# Camera_Schematics.net
KiCad netlist of a schematic drawn in Altium Designer
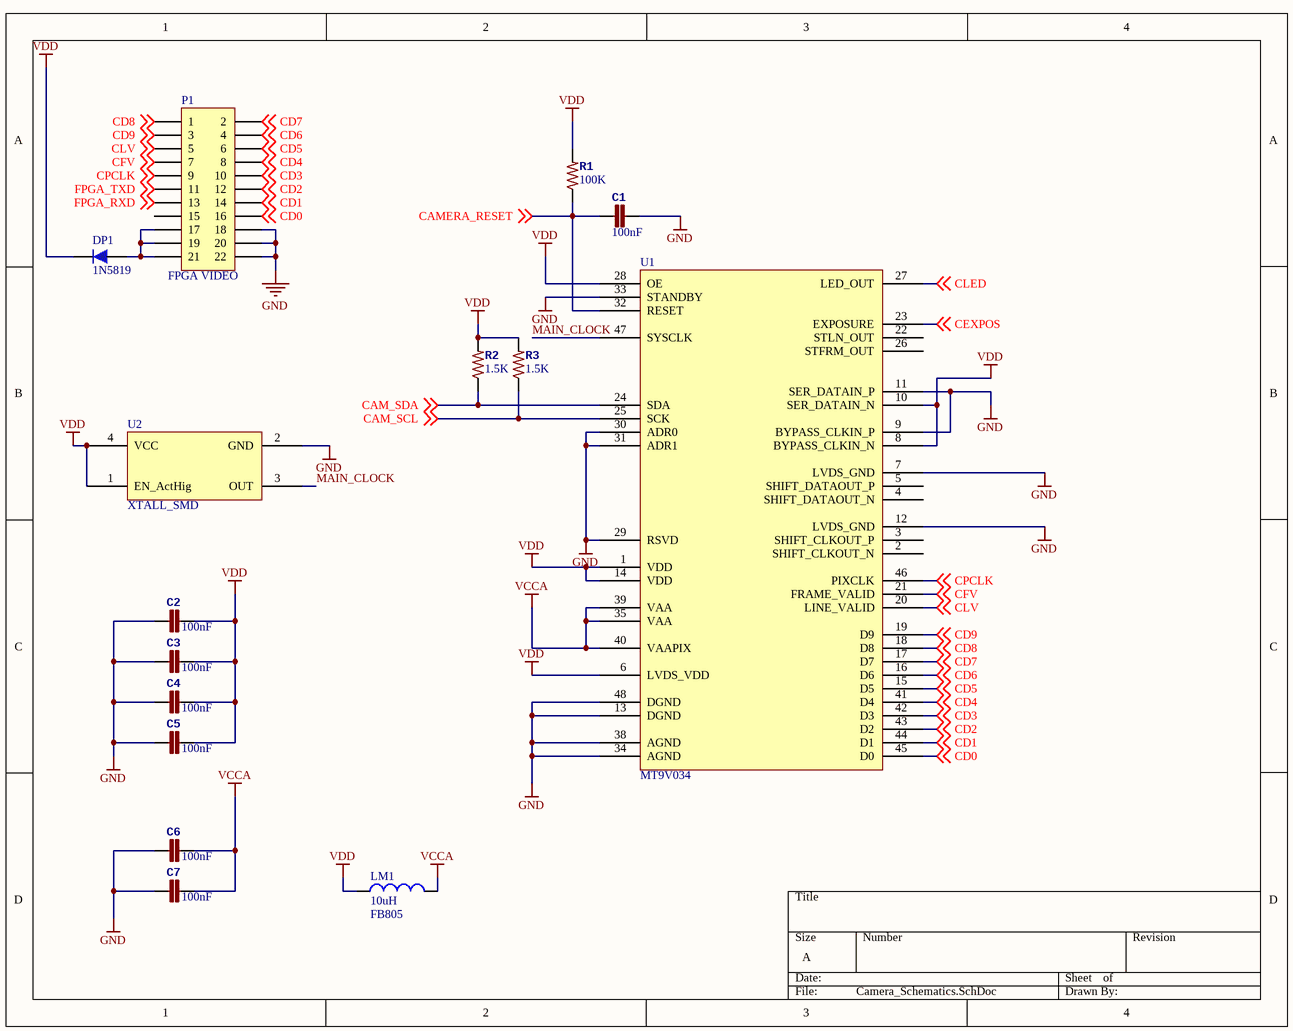
[diagram p0: Camera_Schematics.SchDoc]

(export (version "E")
  (design (tool "Eeschema 10.0.6"))
  (components
    (comp (ref "C1")
      (value "100nF")
      (footprint "_0805")
      (fields (field (name "Comment") "Cap"))
      (libsource (lib "Passives_Integrated_Library") (part "Cap_1"))
    )
    (comp (ref "C2")
      (value "100nF")
      (footprint "_0805")
      (fields (field (name "Comment") "Cap"))
      (libsource (lib "Passives_Integrated_Library") (part "Cap_1"))
    )
    (comp (ref "C3")
      (value "100nF")
      (footprint "_0805")
      (fields (field (name "Comment") "Cap"))
      (libsource (lib "Passives_Integrated_Library") (part "Cap_1"))
    )
    (comp (ref "C4")
      (value "100nF")
      (footprint "_0805")
      (fields (field (name "Comment") "Cap"))
      (libsource (lib "Passives_Integrated_Library") (part "Cap_1"))
    )
    (comp (ref "C5")
      (value "100nF")
      (footprint "_0805")
      (fields (field (name "Comment") "Cap"))
      (libsource (lib "Passives_Integrated_Library") (part "Cap_1"))
    )
    (comp (ref "C6")
      (value "100nF")
      (footprint "_0805")
      (fields (field (name "Comment") "Cap"))
      (libsource (lib "Passives_Integrated_Library") (part "Cap_1"))
    )
    (comp (ref "C7")
      (value "100nF")
      (footprint "_0805")
      (fields (field (name "Comment") "Cap"))
      (libsource (lib "Passives_Integrated_Library") (part "Cap_1"))
    )
    (comp (ref "DP1")
      (value "1N5819")
      (footprint "430X270D")
      (description "Schottkey Rectifiers")
      (fields (field (name "DESIGNER") "Abbas Basereh"))
      (libsource (lib "Diodes_Integrated_Library") (part "1N5819"))
    )
    (comp (ref "LM1")
      (value "10uH")
      (footprint "0805L")
      (description "Inductor")
      (fields (field (name "ALTIUM_VALUE") "FB805") (field (name "PUBLISHER") "Altium Limited"))
      (libsource (lib "Passives_Integrated_Library") (part "L SMA 0.25W"))
    )
    (comp (ref "P1")
      (value "FPGA VIDEO")
      (footprint "HDR2X11")
      (description "Header, 11-Pin, Dual row")
      (fields (field (name "PUBLISHER") "Altium Limited"))
      (libsource (lib "Miscellaneous Connectors") (part "Header 11X2"))
    )
    (comp (ref "R1")
      (value "100K")
      (footprint "_0603")
      (fields (field (name "Comment") "Resistor"))
      (libsource (lib "Passives_Integrated_Library") (part "Resistor"))
    )
    (comp (ref "R2")
      (value "1.5K")
      (footprint "_0603")
      (fields (field (name "Comment") "Resistor"))
      (libsource (lib "Passives_Integrated_Library") (part "Resistor"))
    )
    (comp (ref "R3")
      (value "1.5K")
      (footprint "_0603")
      (fields (field (name "Comment") "Resistor"))
      (libsource (lib "Passives_Integrated_Library") (part "Resistor"))
    )
    (comp (ref "U1")
      (value "MT9V034")
      (footprint "MT9V034")
      (libsource (lib "Sensors_Integrated_Library") (part "MT9V034"))
    )
    (comp (ref "U2")
      (value "XTALL_SMD")
      (footprint "XTAL_SMD")
      (libsource (lib "Passives_Integrated_Library") (part "XTAL_SMD"))
    )
  )
  (nets
    (net (code "1") (name "/MAIN_CLOCK") (class "Default")
      (node (ref "U1") (pin "47") (pinfunction "SYSCLK_47") (pintype "passive"))
      (node (ref "U2") (pin "3") (pinfunction "OUT_3") (pintype "passive"))
    )
    (net (code "2") (name "CAMERA_RESET") (class "Default")
      (node (ref "C1") (pin "1") (pinfunction "1_1") (pintype "passive"))
      (node (ref "R1") (pin "1") (pinfunction "1_1") (pintype "passive"))
      (node (ref "U1") (pin "32") (pinfunction "RESET_32") (pintype "passive"))
    )
    (net (code "3") (name "CAM_SCL") (class "Default")
      (node (ref "R3") (pin "1") (pinfunction "1_1") (pintype "passive"))
      (node (ref "U1") (pin "25") (pinfunction "SCK_25") (pintype "passive"))
    )
    (net (code "4") (name "CAM_SDA") (class "Default")
      (node (ref "R2") (pin "1") (pinfunction "1_1") (pintype "passive"))
      (node (ref "U1") (pin "24") (pinfunction "SDA_24") (pintype "passive"))
    )
    (net (code "5") (name "CD0") (class "Default")
      (node (ref "P1") (pin "16") (pinfunction "16_16") (pintype "passive"))
      (node (ref "U1") (pin "45") (pinfunction "D0_45") (pintype "passive"))
    )
    (net (code "6") (name "CD1") (class "Default")
      (node (ref "P1") (pin "14") (pinfunction "14_14") (pintype "passive"))
      (node (ref "U1") (pin "44") (pinfunction "D1_44") (pintype "passive"))
    )
    (net (code "7") (name "CD2") (class "Default")
      (node (ref "P1") (pin "12") (pinfunction "12_12") (pintype "passive"))
      (node (ref "U1") (pin "43") (pinfunction "D2_43") (pintype "passive"))
    )
    (net (code "8") (name "CD3") (class "Default")
      (node (ref "P1") (pin "10") (pinfunction "10_10") (pintype "passive"))
      (node (ref "U1") (pin "42") (pinfunction "D3_42") (pintype "passive"))
    )
    (net (code "9") (name "CD4") (class "Default")
      (node (ref "P1") (pin "8") (pinfunction "8_8") (pintype "passive"))
      (node (ref "U1") (pin "41") (pinfunction "D4_41") (pintype "passive"))
    )
    (net (code "10") (name "CD5") (class "Default")
      (node (ref "P1") (pin "6") (pinfunction "6_6") (pintype "passive"))
      (node (ref "U1") (pin "15") (pinfunction "D5_15") (pintype "passive"))
    )
    (net (code "11") (name "CD6") (class "Default")
      (node (ref "P1") (pin "4") (pinfunction "4_4") (pintype "passive"))
      (node (ref "U1") (pin "16") (pinfunction "D6_16") (pintype "passive"))
    )
    (net (code "12") (name "CD7") (class "Default")
      (node (ref "P1") (pin "2") (pinfunction "2_2") (pintype "passive"))
      (node (ref "U1") (pin "17") (pinfunction "D7_17") (pintype "passive"))
    )
    (net (code "13") (name "CD8") (class "Default")
      (node (ref "P1") (pin "1") (pinfunction "1_1") (pintype "passive"))
      (node (ref "U1") (pin "18") (pinfunction "D8_18") (pintype "passive"))
    )
    (net (code "14") (name "CD9") (class "Default")
      (node (ref "P1") (pin "3") (pinfunction "3_3") (pintype "passive"))
      (node (ref "U1") (pin "19") (pinfunction "D9_19") (pintype "passive"))
    )
    (net (code "15") (name "CEXPOS") (class "Default")
      (node (ref "U1") (pin "23") (pinfunction "EXPOSURE_23") (pintype "passive"))
    )
    (net (code "16") (name "CFV") (class "Default")
      (node (ref "P1") (pin "7") (pinfunction "7_7") (pintype "passive"))
      (node (ref "U1") (pin "21") (pinfunction "FRAME_VALID_21") (pintype "passive"))
    )
    (net (code "17") (name "CLED") (class "Default")
      (node (ref "U1") (pin "27") (pinfunction "LED_OUT_27") (pintype "passive"))
    )
    (net (code "18") (name "CLV") (class "Default")
      (node (ref "P1") (pin "5") (pinfunction "5_5") (pintype "passive"))
      (node (ref "U1") (pin "20") (pinfunction "LINE_VALID_20") (pintype "passive"))
    )
    (net (code "19") (name "CPCLK") (class "Default")
      (node (ref "P1") (pin "9") (pinfunction "9_9") (pintype "passive"))
      (node (ref "U1") (pin "46") (pinfunction "PIXCLK_46") (pintype "passive"))
    )
    (net (code "20") (name "FPGA_RXD") (class "Default")
      (node (ref "P1") (pin "13") (pinfunction "13_13") (pintype "passive"))
    )
    (net (code "21") (name "FPGA_TXD") (class "Default")
      (node (ref "P1") (pin "11") (pinfunction "11_11") (pintype "passive"))
    )
    (net (code "22") (name "GND") (class "Default")
      (node (ref "C1") (pin "2") (pinfunction "2_2") (pintype "passive"))
      (node (ref "C2") (pin "1") (pinfunction "1_1") (pintype "passive"))
      (node (ref "C3") (pin "1") (pinfunction "1_1") (pintype "passive"))
      (node (ref "C4") (pin "1") (pinfunction "1_1") (pintype "passive"))
      (node (ref "C5") (pin "1") (pinfunction "1_1") (pintype "passive"))
      (node (ref "C6") (pin "1") (pinfunction "1_1") (pintype "passive"))
      (node (ref "C7") (pin "1") (pinfunction "1_1") (pintype "passive"))
      (node (ref "P1") (pin "18") (pinfunction "18_18") (pintype "passive"))
      (node (ref "P1") (pin "20") (pinfunction "20_20") (pintype "passive"))
      (node (ref "P1") (pin "22") (pinfunction "22_22") (pintype "passive"))
      (node (ref "U1") (pin "11") (pinfunction "SER_DATAIN_P_11") (pintype "passive"))
      (node (ref "U1") (pin "12") (pinfunction "LVDS_GND_12") (pintype "passive"))
      (node (ref "U1") (pin "13") (pinfunction "DGND_13") (pintype "passive"))
      (node (ref "U1") (pin "29") (pinfunction "RSVD_29") (pintype "passive"))
      (node (ref "U1") (pin "30") (pinfunction "ADR0_30") (pintype "passive"))
      (node (ref "U1") (pin "31") (pinfunction "ADR1_31") (pintype "passive"))
      (node (ref "U1") (pin "33") (pinfunction "STANDBY_33") (pintype "passive"))
      (node (ref "U1") (pin "34") (pinfunction "AGND_34") (pintype "passive"))
      (node (ref "U1") (pin "38") (pinfunction "AGND_38") (pintype "passive"))
      (node (ref "U1") (pin "48") (pinfunction "DGND_48") (pintype "passive"))
      (node (ref "U1") (pin "7") (pinfunction "LVDS_GND_7") (pintype "passive"))
      (node (ref "U1") (pin "9") (pinfunction "BYPASS_CLKIN_P_9") (pintype "passive"))
      (node (ref "U2") (pin "2") (pinfunction "GND_2") (pintype "passive"))
    )
    (net (code "23") (name "Net-(DP1-Pad1)") (class "Default")
      (node (ref "DP1") (pin "1") (pintype "passive"))
      (node (ref "P1") (pin "17") (pinfunction "17_17") (pintype "passive"))
      (node (ref "P1") (pin "19") (pinfunction "19_19") (pintype "passive"))
      (node (ref "P1") (pin "21") (pinfunction "21_21") (pintype "passive"))
    )
    (net (code "24") (name "VCCA") (class "Default")
      (node (ref "C6") (pin "2") (pinfunction "2_2") (pintype "passive"))
      (node (ref "C7") (pin "2") (pinfunction "2_2") (pintype "passive"))
      (node (ref "LM1") (pin "2") (pinfunction "2_2") (pintype "passive"))
      (node (ref "U1") (pin "35") (pinfunction "VAA_35") (pintype "passive"))
      (node (ref "U1") (pin "39") (pinfunction "VAA_39") (pintype "passive"))
      (node (ref "U1") (pin "40") (pinfunction "VAAPIX_40") (pintype "passive"))
    )
    (net (code "25") (name "VDD") (class "Default")
      (node (ref "C2") (pin "2") (pinfunction "2_2") (pintype "passive"))
      (node (ref "C3") (pin "2") (pinfunction "2_2") (pintype "passive"))
      (node (ref "C4") (pin "2") (pinfunction "2_2") (pintype "passive"))
      (node (ref "C5") (pin "2") (pinfunction "2_2") (pintype "passive"))
      (node (ref "DP1") (pin "2") (pintype "passive"))
      (node (ref "LM1") (pin "1") (pinfunction "1_1") (pintype "passive"))
      (node (ref "R1") (pin "2") (pinfunction "2_2") (pintype "passive"))
      (node (ref "R2") (pin "2") (pinfunction "2_2") (pintype "passive"))
      (node (ref "R3") (pin "2") (pinfunction "2_2") (pintype "passive"))
      (node (ref "U1") (pin "1") (pinfunction "VDD_1") (pintype "passive"))
      (node (ref "U1") (pin "10") (pinfunction "SER_DATAIN_N_10") (pintype "passive"))
      (node (ref "U1") (pin "14") (pinfunction "VDD_14") (pintype "passive"))
      (node (ref "U1") (pin "28") (pinfunction "OE_28") (pintype "passive"))
      (node (ref "U1") (pin "6") (pinfunction "LVDS_VDD_6") (pintype "passive"))
      (node (ref "U1") (pin "8") (pinfunction "BYPASS_CLKIN_N_8") (pintype "passive"))
      (node (ref "U2") (pin "1") (pinfunction "EN_ActHig_1") (pintype "passive"))
      (node (ref "U2") (pin "4") (pinfunction "VCC_4") (pintype "passive"))
    )
    (net (code "26") (name "unconnected-(P1-Pad15)") (class "Default")
      (node (ref "P1") (pin "15") (pinfunction "15_15") (pintype "passive"))
    )
    (net (code "27") (name "unconnected-(U1-SHIFT_CLKOUT_N-Pad2)") (class "Default")
      (node (ref "U1") (pin "2") (pinfunction "SHIFT_CLKOUT_N_2") (pintype "passive"))
    )
    (net (code "28") (name "unconnected-(U1-SHIFT_CLKOUT_P-Pad3)") (class "Default")
      (node (ref "U1") (pin "3") (pinfunction "SHIFT_CLKOUT_P_3") (pintype "passive"))
    )
    (net (code "29") (name "unconnected-(U1-SHIFT_DATAOUT_N-Pad4)") (class "Default")
      (node (ref "U1") (pin "4") (pinfunction "SHIFT_DATAOUT_N_4") (pintype "passive"))
    )
    (net (code "30") (name "unconnected-(U1-SHIFT_DATAOUT_P-Pad5)") (class "Default")
      (node (ref "U1") (pin "5") (pinfunction "SHIFT_DATAOUT_P_5") (pintype "passive"))
    )
    (net (code "31") (name "unconnected-(U1-STFRM_OUT-Pad26)") (class "Default")
      (node (ref "U1") (pin "26") (pinfunction "STFRM_OUT_26") (pintype "passive"))
    )
    (net (code "32") (name "unconnected-(U1-STLN_OUT-Pad22)") (class "Default")
      (node (ref "U1") (pin "22") (pinfunction "STLN_OUT_22") (pintype "passive"))
    )
  )
)
